# V1_5.net
KiCad netlist of a schematic drawn in EAGLE
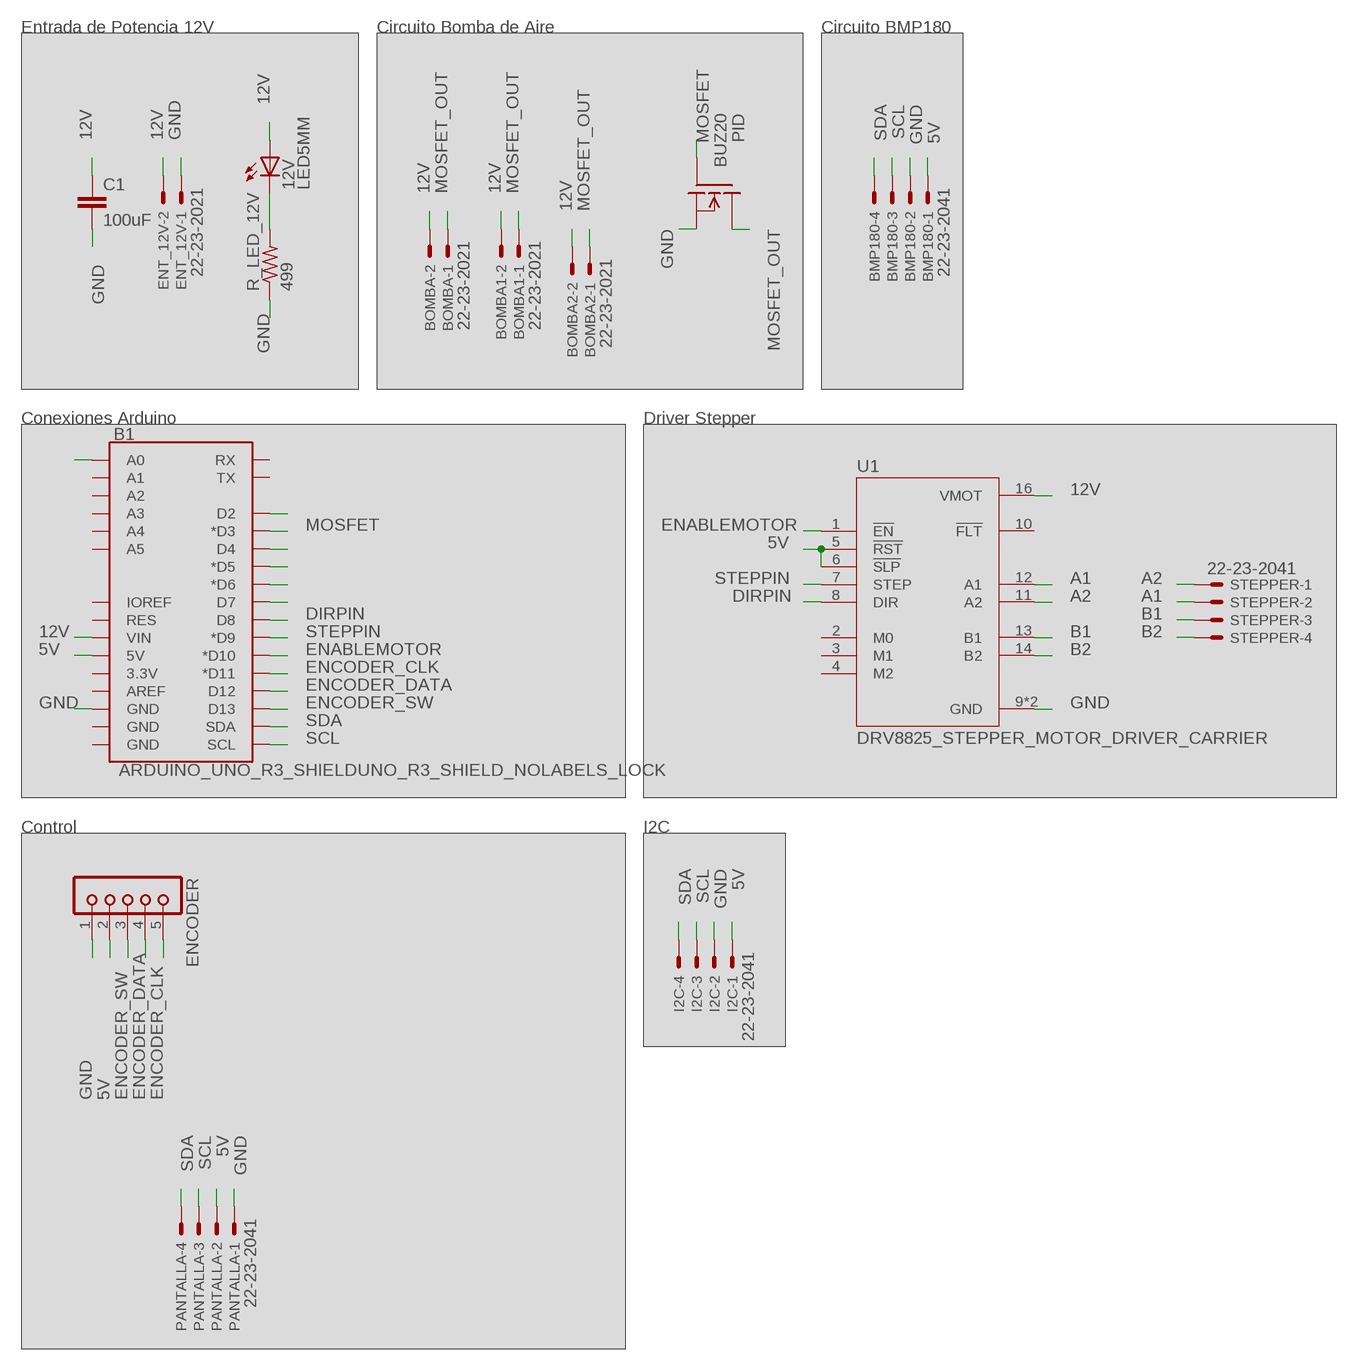
[diagram p0: schematic, sheet 1]

(export (version "E")
  (design (tool "Eeschema 10.0.6"))
  (components
    (comp (ref "12V")
      (value "LED5MM")
      (footprint "eagle-import:5MM")
      (libsource (lib "eagle-import") (part "LED5MM"))
    )
    (comp (ref "B1")
      (value "ARDUINO_UNO_R3_SHIELDUNO_R3_SHIELD_NOLABELS_LOCK")
      (footprint "eagle-import:UNO_R3_SHIELD_NOLABELS_LOCK")
      (libsource (lib "eagle-import") (part "ARDUINO_UNO_R3_SHIELDUNO_R3_SHIELD_NOLABELS_LOCK"))
    )
    (comp (ref "BMP180")
      (value "22-23-2041")
      (footprint "eagle-import:22-23-2041")
      (fields (field (name "MF") "MOLEX"))
      (libsource (lib "eagle-import") (part "22-23-2041"))
    )
    (comp (ref "BOMBA")
      (value "22-23-2021")
      (footprint "eagle-import:22-23-2021")
      (fields (field (name "MF") "MOLEX"))
      (libsource (lib "eagle-import") (part "22-23-2021"))
    )
    (comp (ref "BOMBA1")
      (value "22-23-2021")
      (footprint "eagle-import:22-23-2021")
      (fields (field (name "MF") "MOLEX"))
      (libsource (lib "eagle-import") (part "22-23-2021"))
    )
    (comp (ref "BOMBA2")
      (value "22-23-2021")
      (footprint "eagle-import:22-23-2021")
      (fields (field (name "MF") "MOLEX"))
      (libsource (lib "eagle-import") (part "22-23-2021"))
    )
    (comp (ref "C1")
      (value "100uF")
      (footprint "eagle-import:C2.5-5")
      (libsource (lib "eagle-import") (part "C2.5/5"))
    )
    (comp (ref "ENCODER")
      (value "JU05")
      (footprint "eagle-import:JU05")
      (libsource (lib "eagle-import") (part "JU05"))
    )
    (comp (ref "ENT_12V")
      (value "22-23-2021")
      (footprint "eagle-import:22-23-2021")
      (fields (field (name "MF") "MOLEX"))
      (libsource (lib "eagle-import") (part "22-23-2021"))
    )
    (comp (ref "I2C")
      (value "22-23-2041")
      (footprint "eagle-import:22-23-2041")
      (fields (field (name "MF") "MOLEX"))
      (libsource (lib "eagle-import") (part "22-23-2041"))
    )
    (comp (ref "PANTALLA")
      (value "22-23-2041")
      (footprint "eagle-import:22-23-2041")
      (fields (field (name "MF") "MOLEX"))
      (libsource (lib "eagle-import") (part "22-23-2041"))
    )
    (comp (ref "PID")
      (value "BUZ20")
      (footprint "eagle-import:TO220")
      (libsource (lib "eagle-import") (part "BUZ20"))
    )
    (comp (ref "R_LED_12V")
      (value "499")
      (footprint "eagle-import:0204_7")
      (libsource (lib "eagle-import") (part "R-US_0204/7"))
    )
    (comp (ref "STEPPER")
      (value "22-23-2041")
      (footprint "eagle-import:22-23-2041")
      (fields (field (name "MF") "MOLEX"))
      (libsource (lib "eagle-import") (part "22-23-2041"))
    )
    (comp (ref "U1")
      (value "DRV8825_STEPPER_MOTOR_DRIVER_CARRIER")
      (footprint "eagle-import:IC_DRV8825_STEPPER_MOTOR_DRIVER_CARRIER")
      (fields (field (name "MF") "Pololu") (field (name "MP") "DRV8825 STEPPER MOTOR DRIVER CARRIER"))
      (libsource (lib "eagle-import") (part "DRV8825_STEPPER_MOTOR_DRIVER_CARRIER"))
    )
  )
  (nets
    (net (code "1") (name "/5V") (class "Default")
      (node (ref "B1") (pin "5V") (pinfunction "5V_5V") (pintype "bidirectional"))
      (node (ref "BMP180") (pin "1") (pinfunction "S_1") (pintype "passive"))
      (node (ref "ENCODER") (pin "2") (pinfunction "2_2") (pintype "passive"))
      (node (ref "I2C") (pin "1") (pinfunction "S_1") (pintype "passive"))
      (node (ref "PANTALLA") (pin "2") (pinfunction "S_2") (pintype "passive"))
      (node (ref "U1") (pin "5") (pinfunction "~{RST}_5") (pintype "input"))
      (node (ref "U1") (pin "6") (pinfunction "~{SLP}_6") (pintype "input"))
    )
    (net (code "2") (name "/12V") (class "Default")
      (node (ref "12V") (pin "IN") (pinfunction "A_IN") (pintype "passive"))
      (node (ref "B1") (pin "VIN") (pinfunction "VIN_VIN") (pintype "bidirectional"))
      (node (ref "BOMBA") (pin "2") (pinfunction "S_2") (pintype "passive"))
      (node (ref "BOMBA1") (pin "2") (pinfunction "S_2") (pintype "passive"))
      (node (ref "BOMBA2") (pin "2") (pinfunction "S_2") (pintype "passive"))
      (node (ref "C1") (pin "1") (pinfunction "1_1") (pintype "passive"))
      (node (ref "ENT_12V") (pin "2") (pinfunction "S_2") (pintype "passive"))
      (node (ref "U1") (pin "16") (pinfunction "VMOT_16") (pintype "power_in"))
    )
    (net (code "3") (name "/A1") (class "Default")
      (node (ref "STEPPER") (pin "2") (pinfunction "S_2") (pintype "passive"))
      (node (ref "U1") (pin "12") (pinfunction "A1_12") (pintype "output"))
    )
    (net (code "4") (name "/A2") (class "Default")
      (node (ref "STEPPER") (pin "1") (pinfunction "S_1") (pintype "passive"))
      (node (ref "U1") (pin "11") (pinfunction "A2_11") (pintype "output"))
    )
    (net (code "5") (name "/B1") (class "Default")
      (node (ref "STEPPER") (pin "3") (pinfunction "S_3") (pintype "passive"))
      (node (ref "U1") (pin "13") (pinfunction "B1_13") (pintype "output"))
    )
    (net (code "6") (name "/B2") (class "Default")
      (node (ref "STEPPER") (pin "4") (pinfunction "S_4") (pintype "passive"))
      (node (ref "U1") (pin "14") (pinfunction "B2_14") (pintype "output"))
    )
    (net (code "7") (name "/DIRPIN") (class "Default")
      (node (ref "B1") (pin "D8") (pinfunction "D8_D8") (pintype "bidirectional"))
      (node (ref "U1") (pin "8") (pinfunction "DIR_8") (pintype "input"))
    )
    (net (code "8") (name "/ENABLEMOTOR") (class "Default")
      (node (ref "B1") (pin "D10") (pinfunction "*D10_D10") (pintype "bidirectional"))
      (node (ref "U1") (pin "1") (pinfunction "~{EN}_1") (pintype "input"))
    )
    (net (code "9") (name "/ENCODER_CLK") (class "Default")
      (node (ref "B1") (pin "D11") (pinfunction "*D11_D11") (pintype "bidirectional"))
      (node (ref "ENCODER") (pin "5") (pinfunction "5_5") (pintype "passive"))
    )
    (net (code "10") (name "/ENCODER_DATA") (class "Default")
      (node (ref "B1") (pin "D12") (pinfunction "D12_D12") (pintype "bidirectional"))
      (node (ref "ENCODER") (pin "4") (pinfunction "4_4") (pintype "passive"))
    )
    (net (code "11") (name "/ENCODER_SW") (class "Default")
      (node (ref "B1") (pin "D13") (pinfunction "D13_D13") (pintype "bidirectional"))
      (node (ref "ENCODER") (pin "3") (pinfunction "3_3") (pintype "passive"))
    )
    (net (code "12") (name "/GND") (class "Default")
      (node (ref "B1") (pin "GND@2") (pinfunction "GND_GND@2") (pintype "bidirectional"))
      (node (ref "BMP180") (pin "2") (pinfunction "S_2") (pintype "passive"))
      (node (ref "C1") (pin "2") (pinfunction "2_2") (pintype "passive"))
      (node (ref "ENCODER") (pin "1") (pinfunction "1_1") (pintype "passive"))
      (node (ref "ENT_12V") (pin "1") (pinfunction "S_1") (pintype "passive"))
      (node (ref "I2C") (pin "2") (pinfunction "S_2") (pintype "passive"))
      (node (ref "PANTALLA") (pin "1") (pinfunction "S_1") (pintype "passive"))
      (node (ref "PID") (pin "3") (pinfunction "S_3") (pintype "passive"))
      (node (ref "R_LED_12V") (pin "1") (pinfunction "1_1") (pintype "passive"))
      (node (ref "U1") (pin "15") (pinfunction "GND_15") (pintype "power_in"))
      (node (ref "U1") (pin "9") (pinfunction "GND_9") (pintype "power_in"))
    )
    (net (code "13") (name "/MOSFET") (class "Default")
      (node (ref "B1") (pin "D3") (pinfunction "*D3_D3") (pintype "bidirectional"))
      (node (ref "PID") (pin "1") (pinfunction "G_1") (pintype "passive"))
    )
    (net (code "14") (name "/MOSFET_OUT") (class "Default")
      (node (ref "BOMBA") (pin "1") (pinfunction "S_1") (pintype "passive"))
      (node (ref "BOMBA1") (pin "1") (pinfunction "S_1") (pintype "passive"))
      (node (ref "BOMBA2") (pin "1") (pinfunction "S_1") (pintype "passive"))
      (node (ref "PID") (pin "2") (pinfunction "D_2") (pintype "passive"))
    )
    (net (code "15") (name "/SCL") (class "Default")
      (node (ref "B1") (pin "SCL") (pinfunction "SCL_SCL") (pintype "bidirectional"))
      (node (ref "BMP180") (pin "3") (pinfunction "S_3") (pintype "passive"))
      (node (ref "I2C") (pin "3") (pinfunction "S_3") (pintype "passive"))
      (node (ref "PANTALLA") (pin "3") (pinfunction "S_3") (pintype "passive"))
    )
    (net (code "16") (name "/SDA") (class "Default")
      (node (ref "B1") (pin "SDA") (pinfunction "SDA_SDA") (pintype "bidirectional"))
      (node (ref "BMP180") (pin "4") (pinfunction "S_4") (pintype "passive"))
      (node (ref "I2C") (pin "4") (pinfunction "S_4") (pintype "passive"))
      (node (ref "PANTALLA") (pin "4") (pinfunction "S_4") (pintype "passive"))
    )
    (net (code "17") (name "/STEPPIN") (class "Default")
      (node (ref "B1") (pin "D9") (pinfunction "*D9_D9") (pintype "bidirectional"))
      (node (ref "U1") (pin "7") (pinfunction "STEP_7") (pintype "input"))
    )
    (net (code "18") (name "Net-(12V-C)") (class "Default")
      (node (ref "12V") (pin "OUT") (pinfunction "C_OUT") (pintype "passive"))
      (node (ref "R_LED_12V") (pin "2") (pinfunction "2_2") (pintype "passive"))
    )
    (net (code "19") (name "unconnected-(B1-*D5-PadD5)") (class "Default")
      (node (ref "B1") (pin "D5") (pinfunction "*D5_D5") (pintype "bidirectional"))
    )
    (net (code "20") (name "unconnected-(B1-*D6-PadD6)") (class "Default")
      (node (ref "B1") (pin "D6") (pinfunction "*D6_D6") (pintype "bidirectional"))
    )
    (net (code "21") (name "unconnected-(B1-GND-PadGND@0)") (class "Default")
      (node (ref "B1") (pin "GND@0") (pinfunction "GND_GND@0") (pintype "bidirectional"))
    )
    (net (code "22") (name "unconnected-(B1-GND-PadGND@1)") (class "Default")
      (node (ref "B1") (pin "GND@1") (pinfunction "GND_GND@1") (pintype "bidirectional"))
    )
    (net (code "23") (name "unconnected-(B1-Pad3.3V)") (class "Default")
      (node (ref "B1") (pin "3.3V") (pinfunction "3.3V_3.3V") (pintype "bidirectional"))
    )
    (net (code "24") (name "unconnected-(B1-PadA0)") (class "Default")
      (node (ref "B1") (pin "A0") (pinfunction "A0_A0") (pintype "bidirectional"))
    )
    (net (code "25") (name "unconnected-(B1-PadA1)") (class "Default")
      (node (ref "B1") (pin "A1") (pinfunction "A1_A1") (pintype "bidirectional"))
    )
    (net (code "26") (name "unconnected-(B1-PadA2)") (class "Default")
      (node (ref "B1") (pin "A2") (pinfunction "A2_A2") (pintype "bidirectional"))
    )
    (net (code "27") (name "unconnected-(B1-PadA3)") (class "Default")
      (node (ref "B1") (pin "A3") (pinfunction "A3_A3") (pintype "bidirectional"))
    )
    (net (code "28") (name "unconnected-(B1-PadA4)") (class "Default")
      (node (ref "B1") (pin "A4") (pinfunction "A4_A4") (pintype "bidirectional"))
    )
    (net (code "29") (name "unconnected-(B1-PadA5)") (class "Default")
      (node (ref "B1") (pin "A5") (pinfunction "A5_A5") (pintype "bidirectional"))
    )
    (net (code "30") (name "unconnected-(B1-PadAREF)") (class "Default")
      (node (ref "B1") (pin "AREF") (pinfunction "AREF_AREF") (pintype "bidirectional"))
    )
    (net (code "31") (name "unconnected-(B1-PadD2)") (class "Default")
      (node (ref "B1") (pin "D2") (pinfunction "D2_D2") (pintype "bidirectional"))
    )
    (net (code "32") (name "unconnected-(B1-PadD4)") (class "Default")
      (node (ref "B1") (pin "D4") (pinfunction "D4_D4") (pintype "bidirectional"))
    )
    (net (code "33") (name "unconnected-(B1-PadD7)") (class "Default")
      (node (ref "B1") (pin "D7") (pinfunction "D7_D7") (pintype "bidirectional"))
    )
    (net (code "34") (name "unconnected-(B1-PadIOREF)") (class "Default")
      (node (ref "B1") (pin "IOREF") (pinfunction "IOREF_IOREF") (pintype "bidirectional"))
    )
    (net (code "35") (name "unconnected-(B1-PadRES)") (class "Default")
      (node (ref "B1") (pin "RES") (pinfunction "RES_RES") (pintype "bidirectional"))
    )
    (net (code "36") (name "unconnected-(B1-PadRX)") (class "Default")
      (node (ref "B1") (pin "RX") (pinfunction "RX_RX") (pintype "bidirectional"))
    )
    (net (code "37") (name "unconnected-(B1-PadTX)") (class "Default")
      (node (ref "B1") (pin "TX") (pinfunction "TX_TX") (pintype "bidirectional"))
    )
    (net (code "38") (name "unconnected-(U1-M0-Pad2)") (class "Default")
      (node (ref "U1") (pin "2") (pinfunction "M0_2") (pintype "input"))
    )
    (net (code "39") (name "unconnected-(U1-M1-Pad3)") (class "Default")
      (node (ref "U1") (pin "3") (pinfunction "M1_3") (pintype "input"))
    )
    (net (code "40") (name "unconnected-(U1-M2-Pad4)") (class "Default")
      (node (ref "U1") (pin "4") (pinfunction "M2_4") (pintype "input"))
    )
    (net (code "41") (name "unconnected-(U1-~{FLT}-Pad10)") (class "Default")
      (node (ref "U1") (pin "10") (pinfunction "~{FLT}_10") (pintype "output"))
    )
  )
)
